# Controller.net
KiCad netlist of a schematic drawn in EAGLE
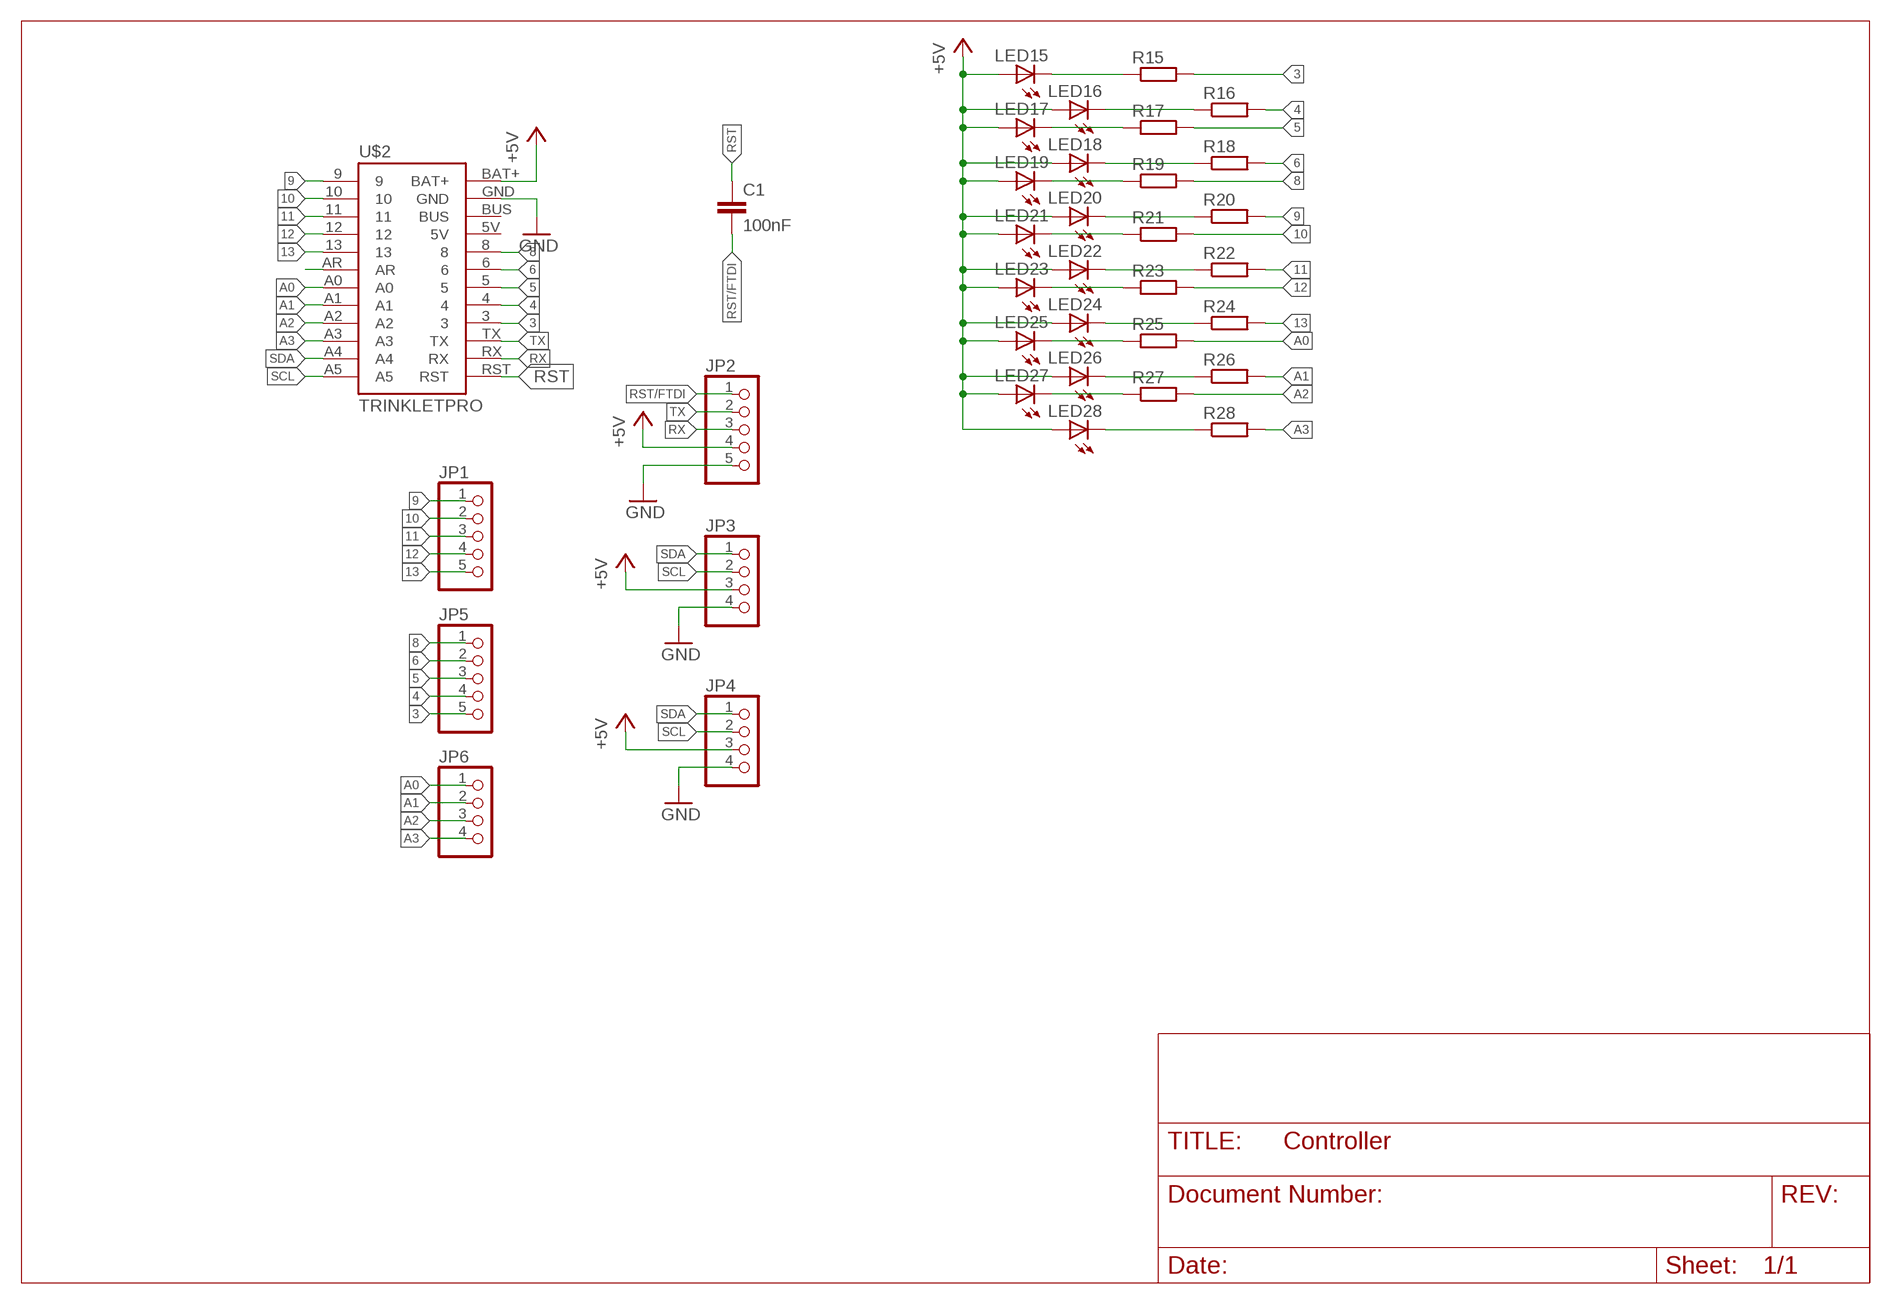
[diagram p0: schematic, sheet 1]

(export (version "E")
  (design (tool "Eeschema 10.0.6"))
  (components
    (comp (ref "C1")
      (value "100nF")
      (footprint "eagle-import:C0805")
      (libsource (lib "eagle-import") (part "C-EUC0805"))
    )
    (comp (ref "JP1")
      (value "PINHD-1X5")
      (footprint "eagle-import:1X05")
      (libsource (lib "eagle-import") (part "PINHD-1X5"))
    )
    (comp (ref "JP2")
      (value "PINHD-1X5")
      (footprint "eagle-import:1X05")
      (libsource (lib "eagle-import") (part "PINHD-1X5"))
    )
    (comp (ref "JP3")
      (value "PINHD-1X4")
      (footprint "eagle-import:1X04")
      (libsource (lib "eagle-import") (part "PINHD-1X4"))
    )
    (comp (ref "JP4")
      (value "PINHD-1X4")
      (footprint "eagle-import:1X04")
      (libsource (lib "eagle-import") (part "PINHD-1X4"))
    )
    (comp (ref "JP5")
      (value "PINHD-1X5")
      (footprint "eagle-import:1X05")
      (libsource (lib "eagle-import") (part "PINHD-1X5"))
    )
    (comp (ref "JP6")
      (value "PINHD-1X4")
      (footprint "eagle-import:1X04")
      (libsource (lib "eagle-import") (part "PINHD-1X4"))
    )
    (comp (ref "LED15")
      (value "LEDCHIP-LED0805")
      (footprint "eagle-import:CHIP-LED0805")
      (libsource (lib "eagle-import") (part "LEDCHIP-LED0805"))
    )
    (comp (ref "LED16")
      (value "LEDCHIP-LED0805")
      (footprint "eagle-import:CHIP-LED0805")
      (libsource (lib "eagle-import") (part "LEDCHIP-LED0805"))
    )
    (comp (ref "LED17")
      (value "LEDCHIP-LED0805")
      (footprint "eagle-import:CHIP-LED0805")
      (libsource (lib "eagle-import") (part "LEDCHIP-LED0805"))
    )
    (comp (ref "LED18")
      (value "LEDCHIP-LED0805")
      (footprint "eagle-import:CHIP-LED0805")
      (libsource (lib "eagle-import") (part "LEDCHIP-LED0805"))
    )
    (comp (ref "LED19")
      (value "LEDCHIP-LED0805")
      (footprint "eagle-import:CHIP-LED0805")
      (libsource (lib "eagle-import") (part "LEDCHIP-LED0805"))
    )
    (comp (ref "LED20")
      (value "LEDCHIP-LED0805")
      (footprint "eagle-import:CHIP-LED0805")
      (libsource (lib "eagle-import") (part "LEDCHIP-LED0805"))
    )
    (comp (ref "LED21")
      (value "LEDCHIP-LED0805")
      (footprint "eagle-import:CHIP-LED0805")
      (libsource (lib "eagle-import") (part "LEDCHIP-LED0805"))
    )
    (comp (ref "LED22")
      (value "LEDCHIP-LED0805")
      (footprint "eagle-import:CHIP-LED0805")
      (libsource (lib "eagle-import") (part "LEDCHIP-LED0805"))
    )
    (comp (ref "LED23")
      (value "LEDCHIP-LED0805")
      (footprint "eagle-import:CHIP-LED0805")
      (libsource (lib "eagle-import") (part "LEDCHIP-LED0805"))
    )
    (comp (ref "LED24")
      (value "LEDCHIP-LED0805")
      (footprint "eagle-import:CHIP-LED0805")
      (libsource (lib "eagle-import") (part "LEDCHIP-LED0805"))
    )
    (comp (ref "LED25")
      (value "LEDCHIP-LED0805")
      (footprint "eagle-import:CHIP-LED0805")
      (libsource (lib "eagle-import") (part "LEDCHIP-LED0805"))
    )
    (comp (ref "LED26")
      (value "LEDCHIP-LED0805")
      (footprint "eagle-import:CHIP-LED0805")
      (libsource (lib "eagle-import") (part "LEDCHIP-LED0805"))
    )
    (comp (ref "LED27")
      (value "LEDCHIP-LED0805")
      (footprint "eagle-import:CHIP-LED0805")
      (libsource (lib "eagle-import") (part "LEDCHIP-LED0805"))
    )
    (comp (ref "LED28")
      (value "LEDCHIP-LED0805")
      (footprint "eagle-import:CHIP-LED0805")
      (libsource (lib "eagle-import") (part "LEDCHIP-LED0805"))
    )
    (comp (ref "R15")
      (value "R-EU_R0805")
      (footprint "eagle-import:R0805")
      (libsource (lib "eagle-import") (part "R-EU_R0805"))
    )
    (comp (ref "R16")
      (value "R-EU_R0805")
      (footprint "eagle-import:R0805")
      (libsource (lib "eagle-import") (part "R-EU_R0805"))
    )
    (comp (ref "R17")
      (value "R-EU_R0805")
      (footprint "eagle-import:R0805")
      (libsource (lib "eagle-import") (part "R-EU_R0805"))
    )
    (comp (ref "R18")
      (value "R-EU_R0805")
      (footprint "eagle-import:R0805")
      (libsource (lib "eagle-import") (part "R-EU_R0805"))
    )
    (comp (ref "R19")
      (value "R-EU_R0805")
      (footprint "eagle-import:R0805")
      (libsource (lib "eagle-import") (part "R-EU_R0805"))
    )
    (comp (ref "R20")
      (value "R-EU_R0805")
      (footprint "eagle-import:R0805")
      (libsource (lib "eagle-import") (part "R-EU_R0805"))
    )
    (comp (ref "R21")
      (value "R-EU_R0805")
      (footprint "eagle-import:R0805")
      (libsource (lib "eagle-import") (part "R-EU_R0805"))
    )
    (comp (ref "R22")
      (value "R-EU_R0805")
      (footprint "eagle-import:R0805")
      (libsource (lib "eagle-import") (part "R-EU_R0805"))
    )
    (comp (ref "R23")
      (value "R-EU_R0805")
      (footprint "eagle-import:R0805")
      (libsource (lib "eagle-import") (part "R-EU_R0805"))
    )
    (comp (ref "R24")
      (value "R-EU_R0805")
      (footprint "eagle-import:R0805")
      (libsource (lib "eagle-import") (part "R-EU_R0805"))
    )
    (comp (ref "R25")
      (value "R-EU_R0805")
      (footprint "eagle-import:R0805")
      (libsource (lib "eagle-import") (part "R-EU_R0805"))
    )
    (comp (ref "R26")
      (value "R-EU_R0805")
      (footprint "eagle-import:R0805")
      (libsource (lib "eagle-import") (part "R-EU_R0805"))
    )
    (comp (ref "R27")
      (value "R-EU_R0805")
      (footprint "eagle-import:R0805")
      (libsource (lib "eagle-import") (part "R-EU_R0805"))
    )
    (comp (ref "R28")
      (value "R-EU_R0805")
      (footprint "eagle-import:R0805")
      (libsource (lib "eagle-import") (part "R-EU_R0805"))
    )
    (comp (ref "U$2")
      (value "TRINKLETPRO")
      (footprint "eagle-import:1X12")
      (libsource (lib "eagle-import") (part "TRINKLETPRO"))
    )
  )
  (nets
    (net (code "1") (name "+5V") (class "Default")
      (node (ref "JP2") (pin "4") (pinfunction "4_4") (pintype "passive"))
      (node (ref "JP3") (pin "3") (pinfunction "3_3") (pintype "passive"))
      (node (ref "JP4") (pin "3") (pinfunction "3_3") (pintype "passive"))
      (node (ref "LED15") (pin "A") (pinfunction "A_A") (pintype "passive"))
      (node (ref "LED16") (pin "A") (pinfunction "A_A") (pintype "passive"))
      (node (ref "LED17") (pin "A") (pinfunction "A_A") (pintype "passive"))
      (node (ref "LED18") (pin "A") (pinfunction "A_A") (pintype "passive"))
      (node (ref "LED19") (pin "A") (pinfunction "A_A") (pintype "passive"))
      (node (ref "LED20") (pin "A") (pinfunction "A_A") (pintype "passive"))
      (node (ref "LED21") (pin "A") (pinfunction "A_A") (pintype "passive"))
      (node (ref "LED22") (pin "A") (pinfunction "A_A") (pintype "passive"))
      (node (ref "LED23") (pin "A") (pinfunction "A_A") (pintype "passive"))
      (node (ref "LED24") (pin "A") (pinfunction "A_A") (pintype "passive"))
      (node (ref "LED25") (pin "A") (pinfunction "A_A") (pintype "passive"))
      (node (ref "LED26") (pin "A") (pinfunction "A_A") (pintype "passive"))
      (node (ref "LED27") (pin "A") (pinfunction "A_A") (pintype "passive"))
      (node (ref "LED28") (pin "A") (pinfunction "A_A") (pintype "passive"))
      (node (ref "U$2") (pin "BAT+") (pinfunction "BAT+_BAT+") (pintype "bidirectional"))
    )
    (net (code "2") (name "3") (class "Default")
      (node (ref "JP5") (pin "5") (pinfunction "5_5") (pintype "passive"))
      (node (ref "R15") (pin "2") (pinfunction "2_2") (pintype "passive"))
      (node (ref "U$2") (pin "3") (pinfunction "3_3") (pintype "bidirectional"))
    )
    (net (code "3") (name "4") (class "Default")
      (node (ref "JP5") (pin "4") (pinfunction "4_4") (pintype "passive"))
      (node (ref "R16") (pin "2") (pinfunction "2_2") (pintype "passive"))
      (node (ref "U$2") (pin "4") (pinfunction "4_4") (pintype "bidirectional"))
    )
    (net (code "4") (name "5") (class "Default")
      (node (ref "JP5") (pin "3") (pinfunction "3_3") (pintype "passive"))
      (node (ref "R17") (pin "2") (pinfunction "2_2") (pintype "passive"))
      (node (ref "U$2") (pin "5") (pinfunction "5_5") (pintype "bidirectional"))
    )
    (net (code "5") (name "6") (class "Default")
      (node (ref "JP5") (pin "2") (pinfunction "2_2") (pintype "passive"))
      (node (ref "R18") (pin "2") (pinfunction "2_2") (pintype "passive"))
      (node (ref "U$2") (pin "6") (pinfunction "6_6") (pintype "bidirectional"))
    )
    (net (code "6") (name "8") (class "Default")
      (node (ref "JP5") (pin "1") (pinfunction "1_1") (pintype "passive"))
      (node (ref "R19") (pin "2") (pinfunction "2_2") (pintype "passive"))
      (node (ref "U$2") (pin "8") (pinfunction "8_8") (pintype "bidirectional"))
    )
    (net (code "7") (name "9") (class "Default")
      (node (ref "JP1") (pin "1") (pinfunction "1_1") (pintype "passive"))
      (node (ref "R20") (pin "2") (pinfunction "2_2") (pintype "passive"))
      (node (ref "U$2") (pin "9") (pinfunction "9_9") (pintype "bidirectional"))
    )
    (net (code "8") (name "10") (class "Default")
      (node (ref "JP1") (pin "2") (pinfunction "2_2") (pintype "passive"))
      (node (ref "R21") (pin "2") (pinfunction "2_2") (pintype "passive"))
      (node (ref "U$2") (pin "10") (pinfunction "10_10") (pintype "bidirectional"))
    )
    (net (code "9") (name "11") (class "Default")
      (node (ref "JP1") (pin "3") (pinfunction "3_3") (pintype "passive"))
      (node (ref "R22") (pin "2") (pinfunction "2_2") (pintype "passive"))
      (node (ref "U$2") (pin "11") (pinfunction "11_11") (pintype "bidirectional"))
    )
    (net (code "10") (name "12") (class "Default")
      (node (ref "JP1") (pin "4") (pinfunction "4_4") (pintype "passive"))
      (node (ref "R23") (pin "2") (pinfunction "2_2") (pintype "passive"))
      (node (ref "U$2") (pin "12") (pinfunction "12_12") (pintype "bidirectional"))
    )
    (net (code "11") (name "13") (class "Default")
      (node (ref "JP1") (pin "5") (pinfunction "5_5") (pintype "passive"))
      (node (ref "R24") (pin "2") (pinfunction "2_2") (pintype "passive"))
      (node (ref "U$2") (pin "13") (pinfunction "13_13") (pintype "bidirectional"))
    )
    (net (code "12") (name "A0") (class "Default")
      (node (ref "JP6") (pin "1") (pinfunction "1_1") (pintype "passive"))
      (node (ref "R25") (pin "2") (pinfunction "2_2") (pintype "passive"))
      (node (ref "U$2") (pin "A0") (pinfunction "A0_A0") (pintype "bidirectional"))
    )
    (net (code "13") (name "A1") (class "Default")
      (node (ref "JP6") (pin "2") (pinfunction "2_2") (pintype "passive"))
      (node (ref "R26") (pin "2") (pinfunction "2_2") (pintype "passive"))
      (node (ref "U$2") (pin "A1") (pinfunction "A1_A1") (pintype "bidirectional"))
    )
    (net (code "14") (name "A2") (class "Default")
      (node (ref "JP6") (pin "3") (pinfunction "3_3") (pintype "passive"))
      (node (ref "R27") (pin "2") (pinfunction "2_2") (pintype "passive"))
      (node (ref "U$2") (pin "A2") (pinfunction "A2_A2") (pintype "bidirectional"))
    )
    (net (code "15") (name "A3") (class "Default")
      (node (ref "JP6") (pin "4") (pinfunction "4_4") (pintype "passive"))
      (node (ref "R28") (pin "2") (pinfunction "2_2") (pintype "passive"))
      (node (ref "U$2") (pin "A3") (pinfunction "A3_A3") (pintype "bidirectional"))
    )
    (net (code "16") (name "GND") (class "Default")
      (node (ref "JP2") (pin "5") (pinfunction "5_5") (pintype "passive"))
      (node (ref "JP3") (pin "4") (pinfunction "4_4") (pintype "passive"))
      (node (ref "JP4") (pin "4") (pinfunction "4_4") (pintype "passive"))
      (node (ref "U$2") (pin "GND") (pinfunction "GND_GND") (pintype "bidirectional"))
    )
    (net (code "17") (name "Net-(LED15-PadC)") (class "Default")
      (node (ref "LED15") (pin "C") (pinfunction "C_C") (pintype "passive"))
      (node (ref "R15") (pin "1") (pinfunction "1_1") (pintype "passive"))
    )
    (net (code "18") (name "Net-(LED16-PadC)") (class "Default")
      (node (ref "LED16") (pin "C") (pinfunction "C_C") (pintype "passive"))
      (node (ref "R16") (pin "1") (pinfunction "1_1") (pintype "passive"))
    )
    (net (code "19") (name "Net-(LED17-PadC)") (class "Default")
      (node (ref "LED17") (pin "C") (pinfunction "C_C") (pintype "passive"))
      (node (ref "R17") (pin "1") (pinfunction "1_1") (pintype "passive"))
    )
    (net (code "20") (name "Net-(LED18-PadC)") (class "Default")
      (node (ref "LED18") (pin "C") (pinfunction "C_C") (pintype "passive"))
      (node (ref "R18") (pin "1") (pinfunction "1_1") (pintype "passive"))
    )
    (net (code "21") (name "Net-(LED19-PadC)") (class "Default")
      (node (ref "LED19") (pin "C") (pinfunction "C_C") (pintype "passive"))
      (node (ref "R19") (pin "1") (pinfunction "1_1") (pintype "passive"))
    )
    (net (code "22") (name "Net-(LED20-PadC)") (class "Default")
      (node (ref "LED20") (pin "C") (pinfunction "C_C") (pintype "passive"))
      (node (ref "R20") (pin "1") (pinfunction "1_1") (pintype "passive"))
    )
    (net (code "23") (name "Net-(LED21-PadC)") (class "Default")
      (node (ref "LED21") (pin "C") (pinfunction "C_C") (pintype "passive"))
      (node (ref "R21") (pin "1") (pinfunction "1_1") (pintype "passive"))
    )
    (net (code "24") (name "Net-(LED22-PadC)") (class "Default")
      (node (ref "LED22") (pin "C") (pinfunction "C_C") (pintype "passive"))
      (node (ref "R22") (pin "1") (pinfunction "1_1") (pintype "passive"))
    )
    (net (code "25") (name "Net-(LED23-PadC)") (class "Default")
      (node (ref "LED23") (pin "C") (pinfunction "C_C") (pintype "passive"))
      (node (ref "R23") (pin "1") (pinfunction "1_1") (pintype "passive"))
    )
    (net (code "26") (name "Net-(LED24-PadC)") (class "Default")
      (node (ref "LED24") (pin "C") (pinfunction "C_C") (pintype "passive"))
      (node (ref "R24") (pin "1") (pinfunction "1_1") (pintype "passive"))
    )
    (net (code "27") (name "Net-(LED25-PadC)") (class "Default")
      (node (ref "LED25") (pin "C") (pinfunction "C_C") (pintype "passive"))
      (node (ref "R25") (pin "1") (pinfunction "1_1") (pintype "passive"))
    )
    (net (code "28") (name "Net-(LED26-PadC)") (class "Default")
      (node (ref "LED26") (pin "C") (pinfunction "C_C") (pintype "passive"))
      (node (ref "R26") (pin "1") (pinfunction "1_1") (pintype "passive"))
    )
    (net (code "29") (name "Net-(LED27-PadC)") (class "Default")
      (node (ref "LED27") (pin "C") (pinfunction "C_C") (pintype "passive"))
      (node (ref "R27") (pin "1") (pinfunction "1_1") (pintype "passive"))
    )
    (net (code "30") (name "Net-(LED28-PadC)") (class "Default")
      (node (ref "LED28") (pin "C") (pinfunction "C_C") (pintype "passive"))
      (node (ref "R28") (pin "1") (pinfunction "1_1") (pintype "passive"))
    )
    (net (code "31") (name "RST") (class "Default")
      (node (ref "C1") (pin "1") (pinfunction "1_1") (pintype "passive"))
      (node (ref "U$2") (pin "RST") (pinfunction "RST_RST") (pintype "bidirectional"))
    )
    (net (code "32") (name "RST{slash}FTDI") (class "Default")
      (node (ref "C1") (pin "2") (pinfunction "2_2") (pintype "passive"))
      (node (ref "JP2") (pin "1") (pinfunction "1_1") (pintype "passive"))
    )
    (net (code "33") (name "RX") (class "Default")
      (node (ref "JP2") (pin "3") (pinfunction "3_3") (pintype "passive"))
      (node (ref "U$2") (pin "RX") (pinfunction "RX_RX") (pintype "bidirectional"))
    )
    (net (code "34") (name "SCL") (class "Default")
      (node (ref "JP3") (pin "2") (pinfunction "2_2") (pintype "passive"))
      (node (ref "JP4") (pin "2") (pinfunction "2_2") (pintype "passive"))
      (node (ref "U$2") (pin "A5") (pinfunction "A5_A5") (pintype "bidirectional"))
    )
    (net (code "35") (name "SDA") (class "Default")
      (node (ref "JP3") (pin "1") (pinfunction "1_1") (pintype "passive"))
      (node (ref "JP4") (pin "1") (pinfunction "1_1") (pintype "passive"))
      (node (ref "U$2") (pin "A4") (pinfunction "A4_A4") (pintype "bidirectional"))
    )
    (net (code "36") (name "TX") (class "Default")
      (node (ref "JP2") (pin "2") (pinfunction "2_2") (pintype "passive"))
      (node (ref "U$2") (pin "TX") (pinfunction "TX_TX") (pintype "bidirectional"))
    )
    (net (code "37") (name "unconnected-(U$2-Pad5V)") (class "Default")
      (node (ref "U$2") (pin "5V") (pinfunction "5V_5V") (pintype "bidirectional"))
    )
    (net (code "38") (name "unconnected-(U$2-PadAR)") (class "Default")
      (node (ref "U$2") (pin "AR") (pinfunction "AR_AR") (pintype "bidirectional"))
    )
    (net (code "39") (name "unconnected-(U$2-PadBUS)") (class "Default")
      (node (ref "U$2") (pin "BUS") (pinfunction "BUS_BUS") (pintype "bidirectional"))
    )
  )
)
